# debug_board.net
KiCad netlist of a schematic drawn in Altium Designer
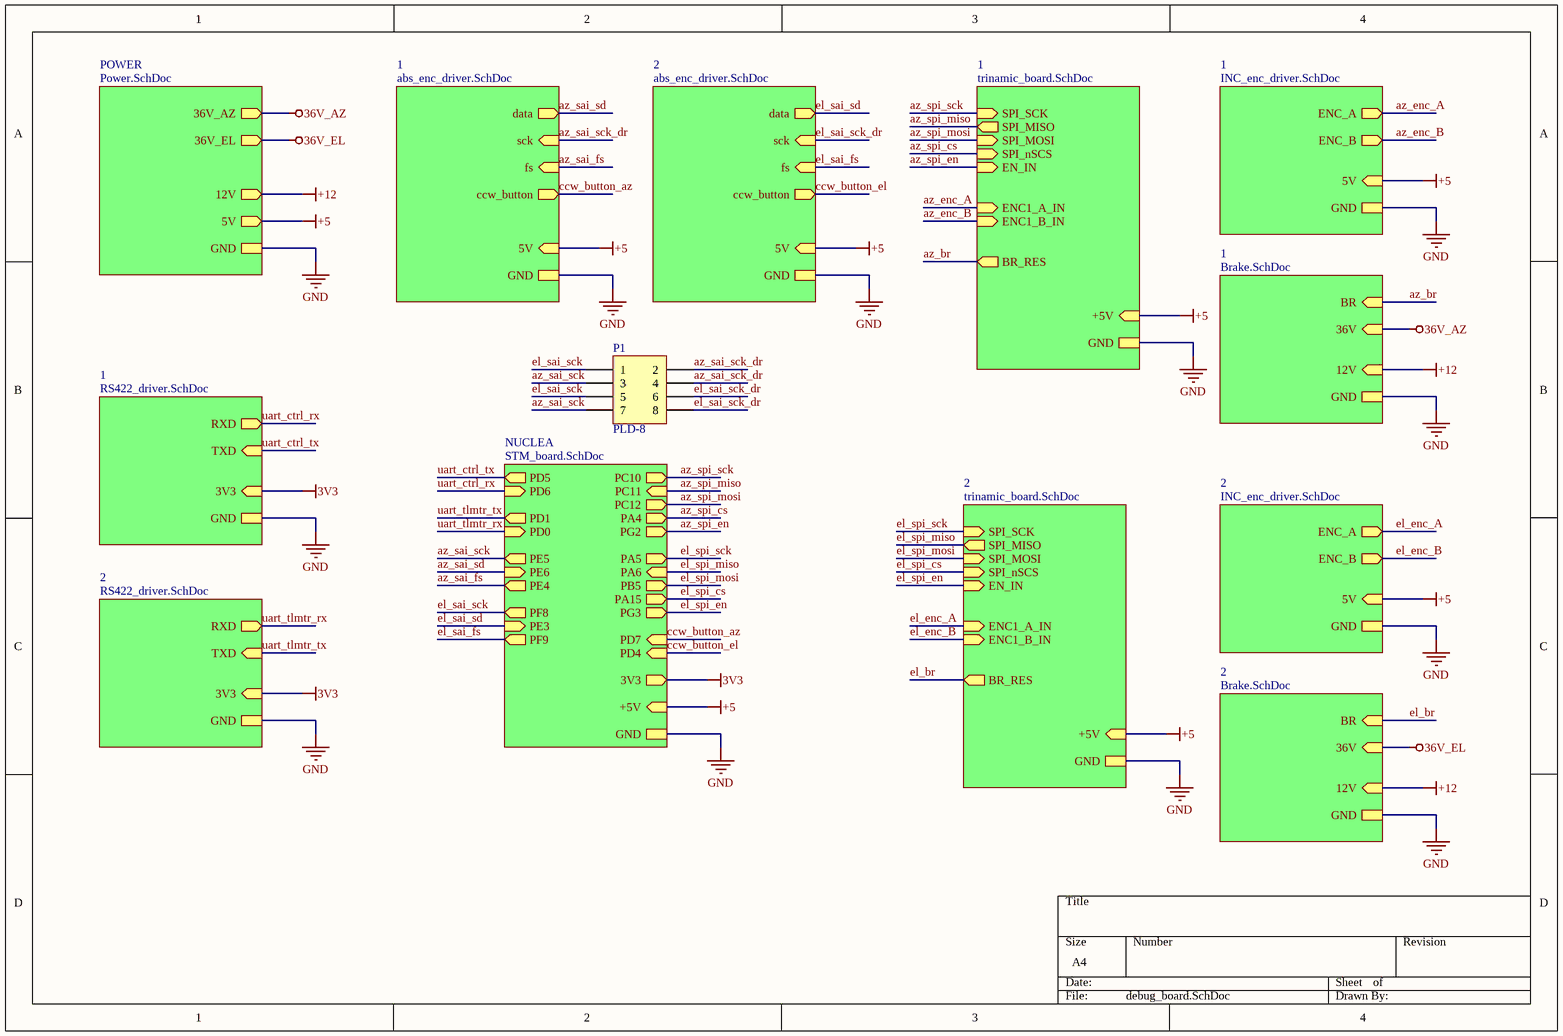
[diagram p0: debug_board.SchDoc]

(export (version "E")
  (design (tool "Eeschema 10.0.6"))
  (components
    (comp (ref "P1")
      (value "PLD-8")
      (footprint "PLD-8")
      (description "Разъем штыревой на плату (папа)")
      (libsource (lib "db") (part "PLD-8"))
    )
  )
  (nets
    (net (code "7") (name "/az_sai_sck") (class "Default")
      (node (ref "P1") (pin "3") (pinfunction "3_3") (pintype "passive"))
      (node (ref "P1") (pin "7") (pinfunction "7_7") (pintype "passive"))
    )
    (net (code "8") (name "/az_sai_sck_dr") (class "Default")
      (node (ref "P1") (pin "2") (pinfunction "2_2") (pintype "passive"))
      (node (ref "P1") (pin "4") (pinfunction "4_4") (pintype "passive"))
    )
    (net (code "21") (name "/el_sai_sck") (class "Default")
      (node (ref "P1") (pin "1") (pinfunction "1_1") (pintype "passive"))
      (node (ref "P1") (pin "5") (pinfunction "5_5") (pintype "passive"))
    )
    (net (code "22") (name "/el_sai_sck_dr") (class "Default")
      (node (ref "P1") (pin "6") (pinfunction "6_6") (pintype "passive"))
      (node (ref "P1") (pin "8") (pinfunction "8_8") (pintype "passive"))
    )
  )
)
